# ATmega324PB_Xplained_Pro_EDBG.net
KiCad netlist of a schematic drawn in Altium Designer
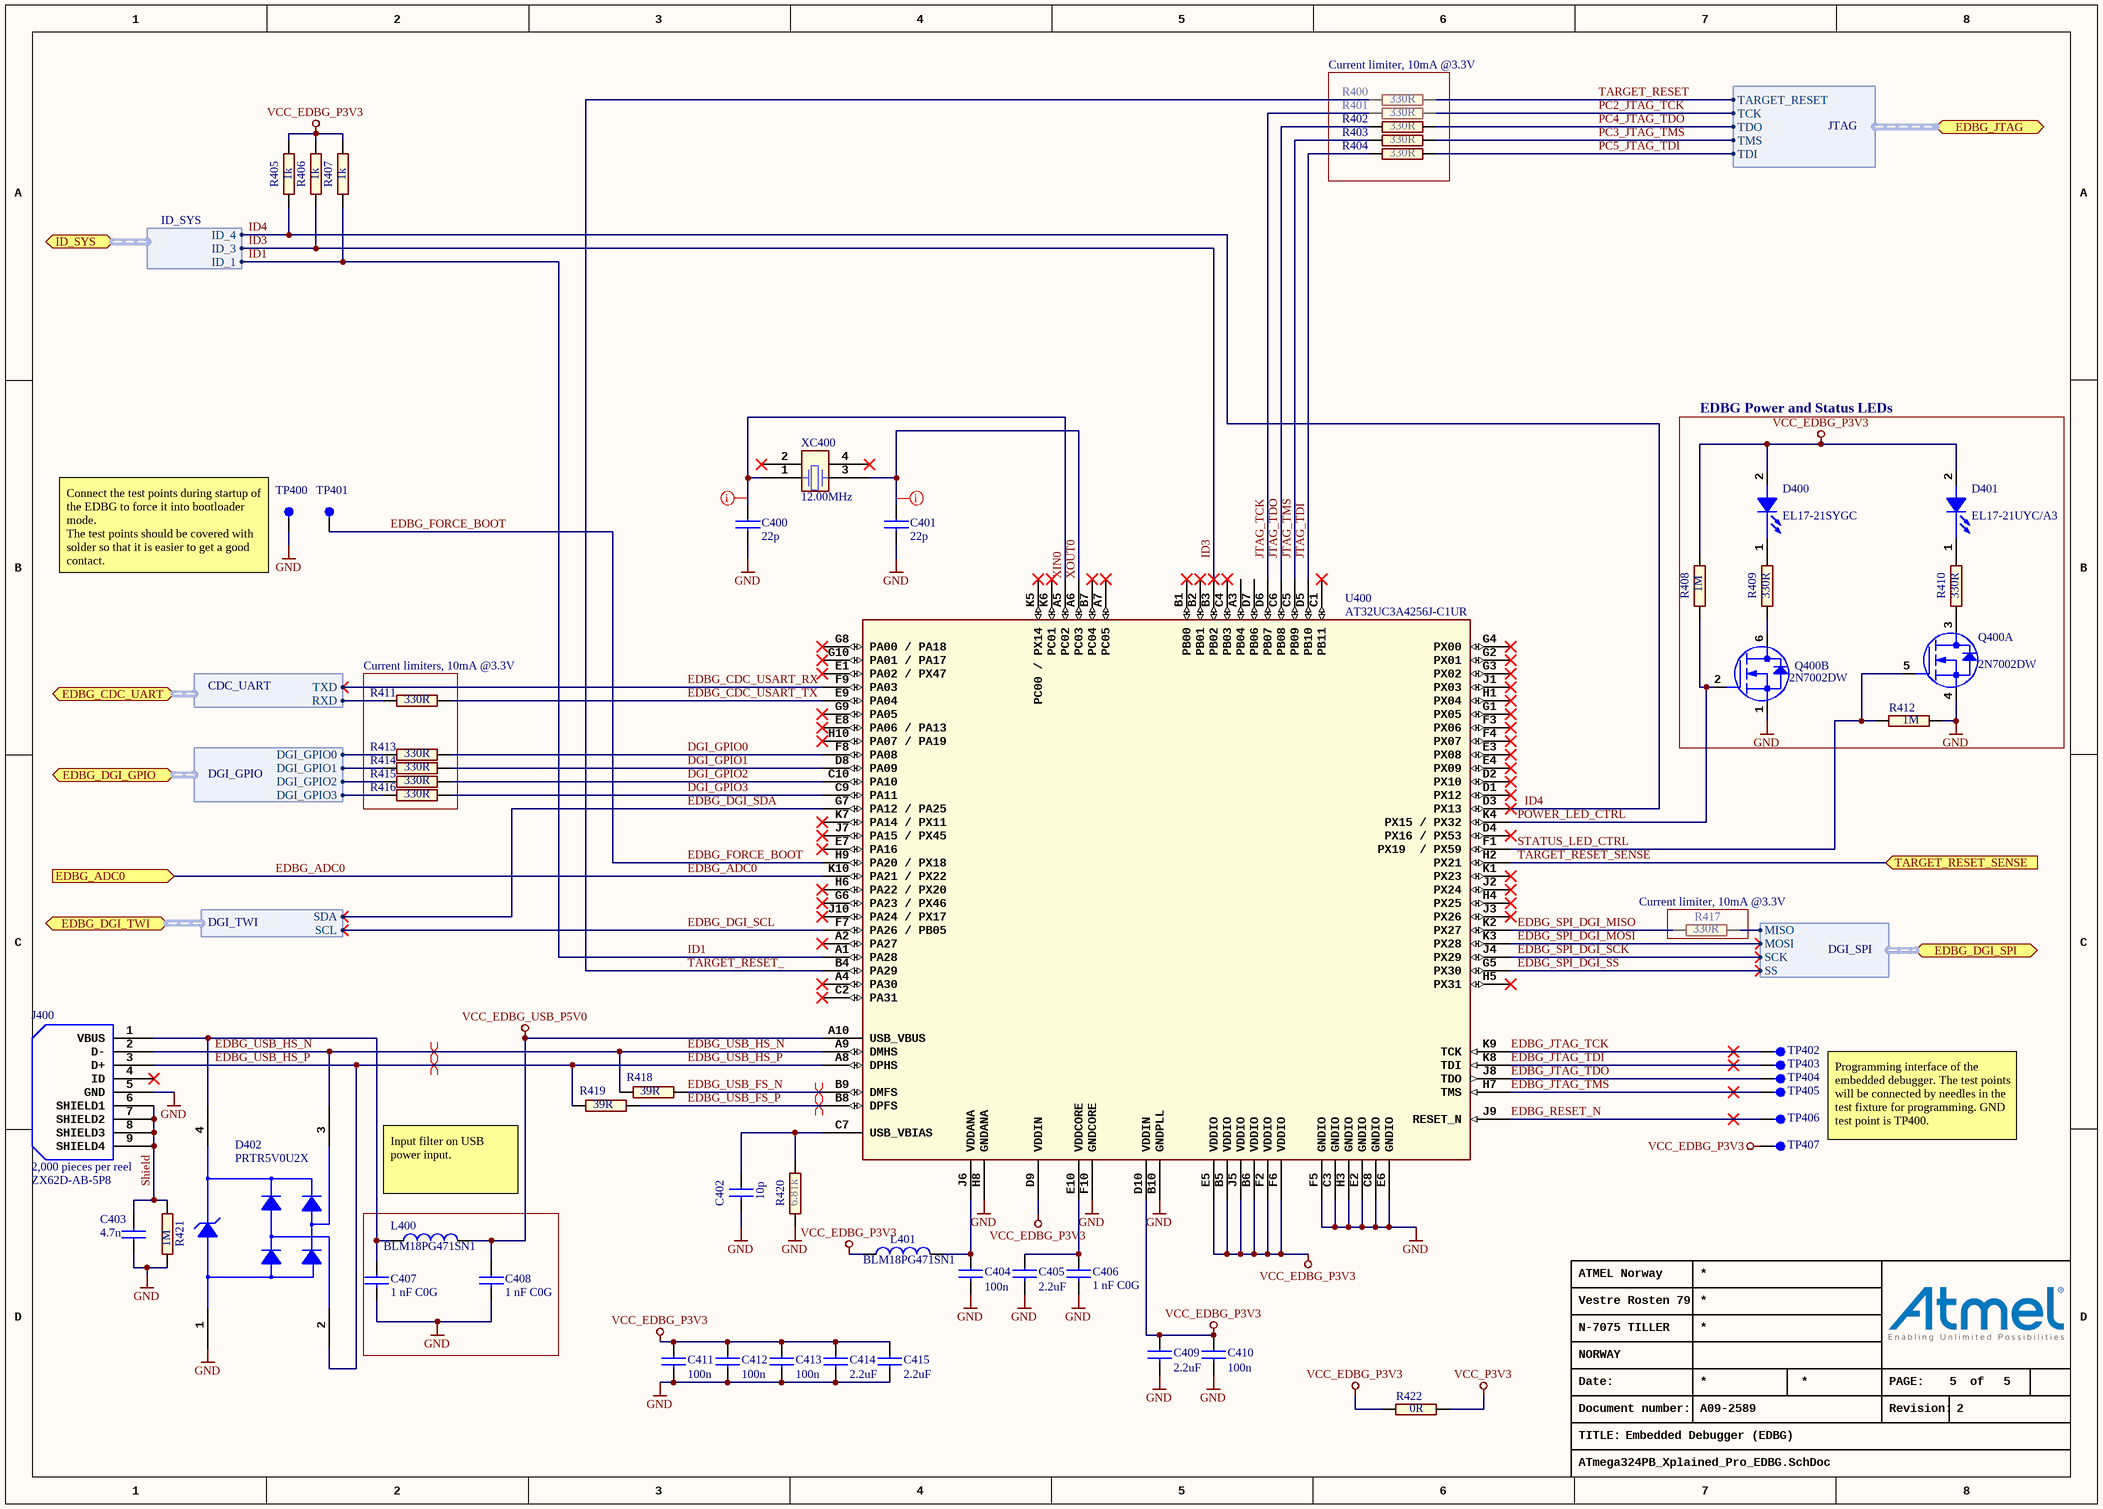
[diagram p0: ATmega324PB_Xplained_Pro_EDBG.SchDoc]

(export (version "E")
  (design (tool "Eeschema 10.0.6"))
  (components
    (comp (ref "C400")
      (value "22p")
      (footprint "AP1-00053")
      (description "Ceramic capacitor, SMD 0402, NP0, 50V, +/-5%")
      (fields (field (name "TOLERANCE") "50V, +/-5%"))
      (libsource (lib "AltiumDbLib") (part "CAP-NONPOL"))
    )
    (comp (ref "C401")
      (value "22p")
      (footprint "AP1-00053")
      (description "Ceramic capacitor, SMD 0402, NP0, 50V, +/-5%")
      (fields (field (name "TOLERANCE") "50V, +/-5%"))
      (libsource (lib "AltiumDbLib") (part "CAP-NONPOL"))
    )
    (comp (ref "C402")
      (value "10p")
      (footprint "AP1-00053")
      (description "Ceramic capacitor, SMD 0402, NP0, 50V, +/-5%")
      (fields (field (name "TOLERANCE") "50V, +/-5%"))
      (libsource (lib "AltiumDbLib") (part "CAP-NONPOL"))
    )
    (comp (ref "C403")
      (value "4.7n")
      (footprint "AP1-00053")
      (description "Ceramic capacitor, SMD 0402, X7R, 25V, +/-10%")
      (fields (field (name "TOLERANCE") "25V, +/-10%"))
      (libsource (lib "AltiumDbLib") (part "CAP-NONPOL"))
    )
    (comp (ref "C404")
      (value "100n")
      (footprint "AP1-00053")
      (description "Ceramic capacitor, SMD 0402, X7R, 16V, +/-10%")
      (fields (field (name "TOLERANCE") "16V, +/-10%") (field (name "MANUFACTURER") "Kemet"))
      (libsource (lib "AltiumDbLib") (part "CAP-NONPOL"))
    )
    (comp (ref "C405")
      (value "2.2uF")
      (footprint "AP1-00053")
      (description "Ceramic capacitor, SMD 0402, X5R, 6.3V, +/-20%")
      (fields (field (name "TOLERANCE") "Â±20%") (field (name "MANUFACTURER") "Kemet"))
      (libsource (lib "AltiumDbLib") (part "CAP-NONPOL"))
    )
    (comp (ref "C406")
      (value "1 nF C0G")
      (footprint "AP1-00053")
      (description "Ceramic capacitor, SMD 0402, C0G, 50V, +/-5%")
      (fields (field (name "TOLERANCE") "5%") (field (name "MANUFACTURER") "Murata"))
      (libsource (lib "AltiumDbLib") (part "CAP-NONPOL"))
    )
    (comp (ref "C407")
      (value "1 nF C0G")
      (footprint "AP1-00053")
      (description "Ceramic capacitor, SMD 0402, C0G, 50V, +/-5%")
      (fields (field (name "TOLERANCE") "5%") (field (name "MANUFACTURER") "Murata"))
      (libsource (lib "AltiumDbLib") (part "CAP-NONPOL"))
    )
    (comp (ref "C408")
      (value "1 nF C0G")
      (footprint "AP1-00053")
      (description "Ceramic capacitor, SMD 0402, C0G, 50V, +/-5%")
      (fields (field (name "TOLERANCE") "5%") (field (name "MANUFACTURER") "Murata"))
      (libsource (lib "AltiumDbLib") (part "CAP-NONPOL"))
    )
    (comp (ref "C409")
      (value "2.2uF")
      (footprint "AP1-00053")
      (description "Ceramic capacitor, SMD 0402, X5R, 6.3V, +/-20%")
      (fields (field (name "TOLERANCE") "Â±20%") (field (name "MANUFACTURER") "Kemet"))
      (libsource (lib "AltiumDbLib") (part "CAP-NONPOL"))
    )
    (comp (ref "C410")
      (value "100n")
      (footprint "AP1-00053")
      (description "Ceramic capacitor, SMD 0402, X7R, 16V, +/-10%")
      (fields (field (name "TOLERANCE") "16V, +/-10%") (field (name "MANUFACTURER") "Kemet"))
      (libsource (lib "AltiumDbLib") (part "CAP-NONPOL"))
    )
    (comp (ref "C411")
      (value "100n")
      (footprint "AP1-00053")
      (description "Ceramic capacitor, SMD 0402, X7R, 16V, +/-10%")
      (fields (field (name "TOLERANCE") "16V, +/-10%") (field (name "MANUFACTURER") "Kemet"))
      (libsource (lib "AltiumDbLib") (part "CAP-NONPOL"))
    )
    (comp (ref "C412")
      (value "100n")
      (footprint "AP1-00053")
      (description "Ceramic capacitor, SMD 0402, X7R, 16V, +/-10%")
      (fields (field (name "TOLERANCE") "16V, +/-10%") (field (name "MANUFACTURER") "Kemet"))
      (libsource (lib "AltiumDbLib") (part "CAP-NONPOL"))
    )
    (comp (ref "C413")
      (value "100n")
      (footprint "AP1-00053")
      (description "Ceramic capacitor, SMD 0402, X7R, 16V, +/-10%")
      (fields (field (name "TOLERANCE") "16V, +/-10%") (field (name "MANUFACTURER") "Kemet"))
      (libsource (lib "AltiumDbLib") (part "CAP-NONPOL"))
    )
    (comp (ref "C414")
      (value "2.2uF")
      (footprint "AP1-00053")
      (description "Ceramic capacitor, SMD 0402, X5R, 6.3V, +/-20%")
      (fields (field (name "TOLERANCE") "Â±20%") (field (name "MANUFACTURER") "Kemet"))
      (libsource (lib "AltiumDbLib") (part "CAP-NONPOL"))
    )
    (comp (ref "C415")
      (value "2.2uF")
      (footprint "AP1-00053")
      (description "Ceramic capacitor, SMD 0402, X5R, 6.3V, +/-20%")
      (fields (field (name "TOLERANCE") "Â±20%") (field (name "MANUFACTURER") "Kemet"))
      (libsource (lib "AltiumDbLib") (part "CAP-NONPOL"))
    )
    (comp (ref "D400")
      (value "EL17-21SYGC")
      (footprint "AP4-00013")
      (description "LED, Green, Wave length=575nm, SMD 0805, ±70°")
      (fields (field (name "MANUFACTURER") "Everlight"))
      (libsource (lib "AltiumDbLib") (part "LED_12"))
    )
    (comp (ref "D401")
      (value "EL17-21UYC/A3")
      (footprint "AP4-00013")
      (description "LED, Yellow, Wave length=591nm, SMD 0805, ±70°")
      (fields (field (name "MANUFACTURER") "Everlight") (field (name "MPN") "17-21UYC/S530-A3/TR8"))
      (libsource (lib "AltiumDbLib") (part "LED_12"))
    )
    (comp (ref "D402")
      (value "PRTR5V0U2X")
      (footprint "AP4-00001")
      (description "Double rail-to-rail USB ESD protection diode")
      (fields
        (field (name "MANUFACTURER") "NXP")
        (field (name "Comment") "Changed manufacturer from Philips to NXP.")
      )
      (libsource (lib "AltiumDbLib") (part "PRTR5V0U2X"))
    )
    (comp (ref "J400")
      (value "2,000 pieces per reel")
      (footprint "AP8-00852")
      (description "Micro USB AB Connector, Standard SMT + DIP")
      (fields
        (field (name "ALTIUM_VALUE") "ZX62D-AB-5P8")
        (field (name "MANUFACTURER") "HIROSE")
        (field (name "MPN") "ZX62D-AB-5P8")
      )
      (libsource (lib "AltiumDbLib") (part "USB_AB"))
    )
    (comp (ref "L400")
      (value "BLM18PG471SN1")
      (footprint "AP3-00005")
      (description "SMD RF inductor 0603. Z=470Ohm (@100MHz), Max R(dc)=0.65Ohm, Max current=1A")
      (fields (field (name "TOLERANCE") "±25%") (field (name "MANUFACTURER") "Murata"))
      (libsource (lib "AltiumDbLib") (part "INDUCTOR"))
    )
    (comp (ref "L401")
      (value "BLM18PG471SN1")
      (footprint "AP3-00005")
      (description "SMD RF inductor 0603. Z=470Ohm (@100MHz), Max R(dc)=0.65Ohm, Max current=1A")
      (fields (field (name "TOLERANCE") "±25%") (field (name "MANUFACTURER") "Murata"))
      (libsource (lib "AltiumDbLib") (part "INDUCTOR"))
    )
    (comp (ref "Q400")
      (value "2N7002DW")
      (footprint "AP5-00001")
      (description "Dual N-Channel MOSFET, 60V, 115mA cont,RDS(ON) < 7.5 Ohm @50mA@5V, SOT-363")
      (fields
        (field (name "MANUFACTURER") "Fairchild")
        (field (name "Comment") "Same as 2N7002 but with two MOSFETs in one package")
      )
      (libsource (lib "AltiumDbLib") (part "MOSFET_DUAL_N_S2G2D1S1G1D2"))
    )
    (comp (ref "R400")
      (value "330R")
      (footprint "AP2-00000")
      (description "Thick film resistor, SMD 0402, 1/16W, 1%")
      (fields (field (name "TOLERANCE") "1 %"))
      (libsource (lib "AltiumDbLib") (part "R2"))
    )
    (comp (ref "R401")
      (value "330R")
      (footprint "AP2-00000")
      (description "Thick film resistor, SMD 0402, 1/16W, 1%")
      (fields (field (name "TOLERANCE") "1 %"))
      (libsource (lib "AltiumDbLib") (part "R2"))
    )
    (comp (ref "R402")
      (value "330R")
      (footprint "AP2-00000")
      (description "Thick film resistor, SMD 0402, 1/16W, 1%")
      (fields (field (name "TOLERANCE") "1 %"))
      (libsource (lib "AltiumDbLib") (part "R2"))
    )
    (comp (ref "R403")
      (value "330R")
      (footprint "AP2-00000")
      (description "Thick film resistor, SMD 0402, 1/16W, 1%")
      (fields (field (name "TOLERANCE") "1 %"))
      (libsource (lib "AltiumDbLib") (part "R2"))
    )
    (comp (ref "R404")
      (value "330R")
      (footprint "AP2-00000")
      (description "Thick film resistor, SMD 0402, 1/16W, 1%")
      (fields (field (name "TOLERANCE") "1 %"))
      (libsource (lib "AltiumDbLib") (part "R2"))
    )
    (comp (ref "R405")
      (value "1k")
      (footprint "AP2-00000")
      (description "Thick film resistor, SMD 0402, 1/16W, 1%")
      (fields (field (name "TOLERANCE") "1 %"))
      (libsource (lib "") (part "R2_2"))
    )
    (comp (ref "R406")
      (value "1k")
      (footprint "AP2-00000")
      (description "Thick film resistor, SMD 0402, 1/16W, 1%")
      (fields (field (name "TOLERANCE") "1 %"))
      (libsource (lib "") (part "R2_2"))
    )
    (comp (ref "R407")
      (value "1k")
      (footprint "AP2-00000")
      (description "Thick film resistor, SMD 0402, 1/16W, 1%")
      (fields (field (name "TOLERANCE") "1 %"))
      (libsource (lib "") (part "R2_2"))
    )
    (comp (ref "R408")
      (value "1M")
      (footprint "AP2-00000")
      (description "Thick film resistor, SMD 0402, 1/16W, 1%")
      (fields (field (name "TOLERANCE") "1 %"))
      (libsource (lib "") (part "R2_2"))
    )
    (comp (ref "R409")
      (value "330R")
      (footprint "AP2-00000")
      (description "Thick film resistor, SMD 0402, 1/16W, 1%")
      (fields (field (name "TOLERANCE") "1 %"))
      (libsource (lib "") (part "R2_2"))
    )
    (comp (ref "R410")
      (value "330R")
      (footprint "AP2-00000")
      (description "Thick film resistor, SMD 0402, 1/16W, 1%")
      (fields (field (name "TOLERANCE") "1 %"))
      (libsource (lib "") (part "R2_2"))
    )
    (comp (ref "R411")
      (value "330R")
      (footprint "AP2-00000")
      (description "Thick film resistor, SMD 0402, 1/16W, 1%")
      (fields (field (name "TOLERANCE") "1 %"))
      (libsource (lib "AltiumDbLib") (part "R2"))
    )
    (comp (ref "R412")
      (value "1M")
      (footprint "AP2-00000")
      (description "Thick film resistor, SMD 0402, 1/16W, 1%")
      (fields (field (name "TOLERANCE") "1 %"))
      (libsource (lib "") (part "R2_1"))
    )
    (comp (ref "R413")
      (value "330R")
      (footprint "AP2-00000")
      (description "Thick film resistor, SMD 0402, 1/16W, 1%")
      (fields (field (name "TOLERANCE") "1 %"))
      (libsource (lib "AltiumDbLib") (part "R2"))
    )
    (comp (ref "R414")
      (value "330R")
      (footprint "AP2-00000")
      (description "Thick film resistor, SMD 0402, 1/16W, 1%")
      (fields (field (name "TOLERANCE") "1 %"))
      (libsource (lib "AltiumDbLib") (part "R2"))
    )
    (comp (ref "R415")
      (value "330R")
      (footprint "AP2-00000")
      (description "Thick film resistor, SMD 0402, 1/16W, 1%")
      (fields (field (name "TOLERANCE") "1 %"))
      (libsource (lib "AltiumDbLib") (part "R2"))
    )
    (comp (ref "R416")
      (value "330R")
      (footprint "AP2-00000")
      (description "Thick film resistor, SMD 0402, 1/16W, 1%")
      (fields (field (name "TOLERANCE") "1 %"))
      (libsource (lib "AltiumDbLib") (part "R2"))
    )
    (comp (ref "R417")
      (value "330R")
      (footprint "AP2-00000")
      (description "Thick film resistor, SMD 0402, 1/16W, 1%")
      (fields (field (name "TOLERANCE") "1 %"))
      (libsource (lib "AltiumDbLib") (part "R2"))
    )
    (comp (ref "R418")
      (value "39R")
      (footprint "AP2-00011")
      (description "Thick film resistor, SMD 0402, 1/16W, 1%")
      (fields (field (name "TOLERANCE") "1 %"))
      (libsource (lib "") (part "R2_3"))
    )
    (comp (ref "R419")
      (value "39R")
      (footprint "AP2-00011")
      (description "Thick film resistor, SMD 0402, 1/16W, 1%")
      (fields (field (name "TOLERANCE") "1 %"))
      (libsource (lib "") (part "R2_3"))
    )
    (comp (ref "R420")
      (value "6.81k")
      (footprint "AP2-00011")
      (description "Thick film resistor, SMD 0402, 1/16W, 1%")
      (fields (field (name "TOLERANCE") "1%"))
      (libsource (lib "") (part "R2_2"))
    )
    (comp (ref "R421")
      (value "1M")
      (footprint "AP2-00011")
      (description "Thick film resistor, SMD 0402, 1/16W, 1%")
      (fields (field (name "TOLERANCE") "1 %"))
      (libsource (lib "") (part "R2_4"))
    )
    (comp (ref "R422")
      (value "0R")
      (footprint "AP2-00000")
      (description "Thick film resistor, SMD 0402, 1/16W, 1%")
      (fields (field (name "TOLERANCE") "1 %") (field (name "MANUFACTURER") "(n/a)"))
      (libsource (lib "AltiumDbLib") (part "R2"))
    )
    (comp (ref "TP400")
      (value "~")
      (footprint "AP8-00010")
      (description "Single SMD testpad")
      (libsource (lib "AltiumDbLib") (part "TESTPOINT"))
    )
    (comp (ref "TP401")
      (value "~")
      (footprint "AP8-00010")
      (description "Single SMD testpad")
      (libsource (lib "AltiumDbLib") (part "TESTPOINT"))
    )
    (comp (ref "TP402")
      (value "~")
      (footprint "AP8-00010")
      (description "Single SMD testpad")
      (libsource (lib "AltiumDbLib") (part "TESTPOINT"))
    )
    (comp (ref "TP403")
      (value "~")
      (footprint "AP8-00010")
      (description "Single SMD testpad")
      (libsource (lib "AltiumDbLib") (part "TESTPOINT"))
    )
    (comp (ref "TP404")
      (value "~")
      (footprint "AP8-00010")
      (description "Single SMD testpad")
      (libsource (lib "AltiumDbLib") (part "TESTPOINT"))
    )
    (comp (ref "TP405")
      (value "~")
      (footprint "AP8-00010")
      (description "Single SMD testpad")
      (libsource (lib "AltiumDbLib") (part "TESTPOINT"))
    )
    (comp (ref "TP406")
      (value "~")
      (footprint "AP8-00010")
      (description "Single SMD testpad")
      (libsource (lib "AltiumDbLib") (part "TESTPOINT"))
    )
    (comp (ref "TP407")
      (value "~")
      (footprint "AP8-00010")
      (description "Single SMD testpad")
      (libsource (lib "AltiumDbLib") (part "TESTPOINT"))
    )
    (comp (ref "U400")
      (value "AT32UC3A4256J-C1UR")
      (footprint "AP6-00206")
      (description "AVR 32-bit RISC MCU")
      (fields (field (name "MANUFACTURER") "ATMEL") (field (name "Comment") "100 ball VFBGA"))
      (libsource (lib "AltiumDbLib") (part "AT32UC3A4_VFBGA"))
    )
    (comp (ref "XC400")
      (value "12.00MHz")
      (footprint "AP7-00039")
      (description "Fox FQ5032B 12.0MHz SMD crystal 738B-12")
      (fields (field (name "TOLERANCE") "Â±30ppm") (field (name "MANUFACTURER") "Fox  Electronics"))
      (libsource (lib "AltiumDbLib") (part "CRYSTAL1324"))
    )
  )
  (nets
    (net (code "7") (name "/DGI_GPIO0") (class "Default")
      (node (ref "R413") (pin "2") (pinfunction "2_2") (pintype "passive"))
      (node (ref "U400") (pin "F8") (pinfunction "PA08_F8") (pintype "bidirectional"))
    )
    (net (code "8") (name "/DGI_GPIO1") (class "Default")
      (node (ref "R414") (pin "2") (pinfunction "2_2") (pintype "passive"))
      (node (ref "U400") (pin "D8") (pinfunction "PA09_D8") (pintype "bidirectional"))
    )
    (net (code "9") (name "/DGI_GPIO2") (class "Default")
      (node (ref "R415") (pin "2") (pinfunction "2_2") (pintype "passive"))
      (node (ref "U400") (pin "C10") (pinfunction "PA10_C10") (pintype "bidirectional"))
    )
    (net (code "10") (name "/DGI_GPIO3") (class "Default")
      (node (ref "R416") (pin "2") (pinfunction "2_2") (pintype "passive"))
      (node (ref "U400") (pin "C9") (pinfunction "PA11_C9") (pintype "bidirectional"))
    )
    (net (code "11") (name "/EDBG_ADC0") (class "Default")
      (node (ref "U400") (pin "K10") (pinfunction "PA21_/_PX22_K10") (pintype "bidirectional"))
    )
    (net (code "12") (name "/EDBG_CDC_USART_RX") (class "Default")
      (node (ref "U400") (pin "F9") (pinfunction "PA03_F9") (pintype "bidirectional+no_connect"))
    )
    (net (code "13") (name "/EDBG_CDC_USART_TX") (class "Default")
      (node (ref "R411") (pin "2") (pinfunction "2_2") (pintype "passive"))
      (node (ref "U400") (pin "E9") (pinfunction "PA04_E9") (pintype "bidirectional"))
    )
    (net (code "14") (name "/EDBG_DGI_SCL") (class "Default")
      (node (ref "U400") (pin "F7") (pinfunction "PA26_/_PB05_F7") (pintype "bidirectional+no_connect"))
    )
    (net (code "15") (name "/EDBG_DGI_SDA") (class "Default")
      (node (ref "U400") (pin "G7") (pinfunction "PA12_/_PA25_G7") (pintype "bidirectional+no_connect"))
    )
    (net (code "16") (name "/EDBG_FORCE_BOOT") (class "Default")
      (node (ref "TP401") (pin "1") (pinfunction "1_1") (pintype "passive"))
      (node (ref "U400") (pin "H9") (pinfunction "PA20_/_PX18_H9") (pintype "bidirectional"))
    )
    (net (code "17") (name "/EDBG_JTAG_TCK") (class "Default")
      (node (ref "TP402") (pin "1") (pinfunction "1_1") (pintype "passive"))
      (node (ref "U400") (pin "K9") (pinfunction "TCK_K9") (pintype "input"))
    )
    (net (code "18") (name "/EDBG_JTAG_TDI") (class "Default")
      (node (ref "TP403") (pin "1") (pinfunction "1_1") (pintype "passive"))
      (node (ref "U400") (pin "K8") (pinfunction "TDI_K8") (pintype "input"))
    )
    (net (code "19") (name "/EDBG_JTAG_TDO") (class "Default")
      (node (ref "TP404") (pin "1") (pinfunction "1_1") (pintype "passive"))
      (node (ref "U400") (pin "J8") (pinfunction "TDO_J8") (pintype "output"))
    )
    (net (code "20") (name "/EDBG_JTAG_TMS") (class "Default")
      (node (ref "TP405") (pin "1") (pinfunction "1_1") (pintype "passive"))
      (node (ref "U400") (pin "H7") (pinfunction "TMS_H7") (pintype "input"))
    )
    (net (code "21") (name "/EDBG_RESET_N") (class "Default")
      (node (ref "TP406") (pin "1") (pinfunction "1_1") (pintype "passive"))
      (node (ref "U400") (pin "J9") (pinfunction "RESET_N_J9") (pintype "input"))
    )
    (net (code "22") (name "/EDBG_SPI_DGI_MISO") (class "Default")
      (node (ref "R417") (pin "1") (pinfunction "1_1") (pintype "passive"))
      (node (ref "U400") (pin "K2") (pinfunction "PX27_K2") (pintype "bidirectional"))
    )
    (net (code "23") (name "/EDBG_SPI_DGI_MOSI") (class "Default")
      (node (ref "U400") (pin "K3") (pinfunction "PX28_K3") (pintype "bidirectional+no_connect"))
    )
    (net (code "24") (name "/EDBG_SPI_DGI_SCK") (class "Default")
      (node (ref "U400") (pin "J4") (pinfunction "PX29_J4") (pintype "bidirectional+no_connect"))
    )
    (net (code "25") (name "/EDBG_SPI_DGI_SS") (class "Default")
      (node (ref "U400") (pin "G5") (pinfunction "PX30_G5") (pintype "bidirectional+no_connect"))
    )
    (net (code "26") (name "/EDBG_USB_FS_N") (class "Default")
      (node (ref "R418") (pin "2") (pinfunction "2_2") (pintype "passive"))
      (node (ref "U400") (pin "B9") (pinfunction "DMFS_B9") (pintype "bidirectional"))
    )
    (net (code "27") (name "/EDBG_USB_FS_P") (class "Default")
      (node (ref "R419") (pin "2") (pinfunction "2_2") (pintype "passive"))
      (node (ref "U400") (pin "B8") (pinfunction "DPFS_B8") (pintype "bidirectional"))
    )
    (net (code "28") (name "/EDBG_USB_HS_N") (class "Default")
      (node (ref "D402") (pin "3") (pinfunction "I/O_2_3") (pintype "passive"))
      (node (ref "J400") (pin "2") (pinfunction "D-_2") (pintype "passive"))
      (node (ref "R418") (pin "1") (pinfunction "1_1") (pintype "passive"))
      (node (ref "U400") (pin "A9") (pinfunction "DMHS_A9") (pintype "bidirectional"))
    )
    (net (code "29") (name "/EDBG_USB_HS_P") (class "Default")
      (node (ref "D402") (pin "2") (pinfunction "I/O_1_2") (pintype "passive"))
      (node (ref "J400") (pin "3") (pinfunction "D+_3") (pintype "passive"))
      (node (ref "R419") (pin "1") (pinfunction "1_1") (pintype "passive"))
      (node (ref "U400") (pin "A8") (pinfunction "DPHS_A8") (pintype "bidirectional"))
    )
    (net (code "30") (name "/ID1") (class "Default")
      (node (ref "R407") (pin "1") (pinfunction "1_1") (pintype "passive"))
      (node (ref "U400") (pin "A1") (pinfunction "PA28_A1") (pintype "bidirectional"))
    )
    (net (code "31") (name "/ID3") (class "Default")
      (node (ref "R406") (pin "1") (pinfunction "1_1") (pintype "passive"))
      (node (ref "U400") (pin "B3") (pinfunction "PB02_B3") (pintype "bidirectional"))
    )
    (net (code "32") (name "/ID4") (class "Default")
      (node (ref "R405") (pin "1") (pinfunction "1_1") (pintype "passive"))
      (node (ref "U400") (pin "D3") (pinfunction "PX13_D3") (pintype "bidirectional"))
    )
    (net (code "33") (name "/JTAG_TCK") (class "Default")
      (node (ref "R401") (pin "1") (pinfunction "1_1") (pintype "passive"))
      (node (ref "U400") (pin "D6") (pinfunction "PB07_D6") (pintype "bidirectional"))
    )
    (net (code "34") (name "/JTAG_TDI") (class "Default")
      (node (ref "R404") (pin "1") (pinfunction "1_1") (pintype "passive"))
      (node (ref "U400") (pin "D5") (pinfunction "PB10_D5") (pintype "bidirectional"))
    )
    (net (code "35") (name "/JTAG_TDO") (class "Default")
      (node (ref "R402") (pin "1") (pinfunction "1_1") (pintype "passive"))
      (node (ref "U400") (pin "C6") (pinfunction "PB08_C6") (pintype "bidirectional"))
    )
    (net (code "36") (name "/JTAG_TMS") (class "Default")
      (node (ref "R403") (pin "1") (pinfunction "1_1") (pintype "passive"))
      (node (ref "U400") (pin "C5") (pinfunction "PB09_C5") (pintype "bidirectional"))
    )
    (net (code "37") (name "/MISO") (class "Default")
      (node (ref "R417") (pin "2") (pinfunction "2_2") (pintype "passive"))
    )
    (net (code "38") (name "/PC2_JTAG_TCK") (class "Default")
      (node (ref "R401") (pin "2") (pinfunction "2_2") (pintype "passive"))
    )
    (net (code "39") (name "/PC3_JTAG_TMS") (class "Default")
      (node (ref "R403") (pin "2") (pinfunction "2_2") (pintype "passive"))
    )
    (net (code "40") (name "/PC4_JTAG_TDO") (class "Default")
      (node (ref "R402") (pin "2") (pinfunction "2_2") (pintype "passive"))
    )
    (net (code "41") (name "/PC5_JTAG_TDI") (class "Default")
      (node (ref "R404") (pin "2") (pinfunction "2_2") (pintype "passive"))
    )
    (net (code "42") (name "/POWER_LED_CTRL") (class "Default")
      (node (ref "Q400") (pin "2") (pinfunction "G2_2") (pintype "passive"))
      (node (ref "R408") (pin "1") (pinfunction "1_1") (pintype "passive"))
      (node (ref "U400") (pin "K4") (pinfunction "PX15_/_PX32_K4") (pintype "bidirectional"))
    )
    (net (code "43") (name "/RXD") (class "Default")
      (node (ref "R411") (pin "1") (pinfunction "1_1") (pintype "passive"))
    )
    (net (code "44") (name "/STATUS_LED_CTRL") (class "Default")
      (node (ref "Q400") (pin "5") (pinfunction "G1_5") (pintype "passive"))
      (node (ref "R412") (pin "2") (pinfunction "2_2") (pintype "passive"))
      (node (ref "U400") (pin "F1") (pinfunction "PX19__/_PX59_F1") (pintype "bidirectional"))
    )
    (net (code "45") (name "/Shield") (class "Default")
      (node (ref "C403") (pin "2") (pinfunction "2_2") (pintype "passive"))
      (node (ref "J400") (pin "6") (pinfunction "SHIELD1_6") (pintype "passive"))
      (node (ref "J400") (pin "7") (pinfunction "SHIELD2_7") (pintype "passive"))
      (node (ref "J400") (pin "8") (pinfunction "SHIELD3_8") (pintype "passive"))
      (node (ref "J400") (pin "9") (pinfunction "SHIELD4_9") (pintype "passive"))
      (node (ref "R421") (pin "2") (pinfunction "2_2") (pintype "passive"))
    )
    (net (code "46") (name "/TARGET_RESET") (class "Default")
      (node (ref "R400") (pin "2") (pinfunction "2_2") (pintype "passive"))
    )
    (net (code "47") (name "/TARGET_RESET_") (class "Default")
      (node (ref "R400") (pin "1") (pinfunction "1_1") (pintype "passive"))
      (node (ref "U400") (pin "B4") (pinfunction "PA29_B4") (pintype "bidirectional"))
    )
    (net (code "48") (name "/TARGET_RESET_SENSE") (class "Default")
      (node (ref "U400") (pin "H2") (pinfunction "PX21_H2") (pintype "bidirectional"))
    )
    (net (code "49") (name "/XIN0") (class "Default")
      (node (ref "C400") (pin "1") (pinfunction "1_1") (pintype "passive"))
      (node (ref "U400") (pin "A5") (pinfunction "PC02_A5") (pintype "bidirectional"))
      (node (ref "XC400") (pin "1") (pinfunction "1_1") (pintype "passive"))
    )
    (net (code "50") (name "/XOUT0") (class "Default")
      (node (ref "C401") (pin "1") (pinfunction "1_1") (pintype "passive"))
      (node (ref "U400") (pin "A6") (pinfunction "PC03_A6") (pintype "bidirectional"))
      (node (ref "XC400") (pin "3") (pinfunction "3_3") (pintype "passive"))
    )
    (net (code "57") (name "GND") (class "Default")
      (node (ref "C400") (pin "2") (pinfunction "2_2") (pintype "passive"))
      (node (ref "C401") (pin "2") (pinfunction "2_2") (pintype "passive"))
      (node (ref "C402") (pin "2") (pinfunction "2_2") (pintype "passive"))
      (node (ref "C403") (pin "1") (pinfunction "1_1") (pintype "passive"))
      (node (ref "C404") (pin "2") (pinfunction "2_2") (pintype "passive"))
      (node (ref "C405") (pin "2") (pinfunction "2_2") (pintype "passive"))
      (node (ref "C406") (pin "2") (pinfunction "2_2") (pintype "passive"))
      (node (ref "C407") (pin "2") (pinfunction "2_2") (pintype "passive"))
      (node (ref "C408") (pin "2") (pinfunction "2_2") (pintype "passive"))
      (node (ref "C409") (pin "2") (pinfunction "2_2") (pintype "passive"))
      (node (ref "C410") (pin "2") (pinfunction "2_2") (pintype "passive"))
      (node (ref "C411") (pin "2") (pinfunction "2_2") (pintype "passive"))
      (node (ref "C412") (pin "2") (pinfunction "2_2") (pintype "passive"))
      (node (ref "C413") (pin "2") (pinfunction "2_2") (pintype "passive"))
      (node (ref "C414") (pin "2") (pinfunction "2_2") (pintype "passive"))
      (node (ref "C415") (pin "2") (pinfunction "2_2") (pintype "passive"))
      (node (ref "D402") (pin "1") (pinfunction "GND_1") (pintype "passive"))
      (node (ref "J400") (pin "5") (pinfunction "GND_5") (pintype "passive"))
      (node (ref "Q400") (pin "1") (pinfunction "S2_1") (pintype "passive"))
      (node (ref "Q400") (pin "4") (pinfunction "S1_4") (pintype "passive"))
      (node (ref "R412") (pin "1") (pinfunction "1_1") (pintype "passive"))
      (node (ref "R420") (pin "1") (pinfunction "1_1") (pintype "passive"))
      (node (ref "R421") (pin "1") (pinfunction "1_1") (pintype "passive"))
      (node (ref "TP400") (pin "1") (pinfunction "1_1") (pintype "passive"))
      (node (ref "U400") (pin "B10") (pinfunction "GNDPLL_B10") (pintype "power_in"))
      (node (ref "U400") (pin "C3") (pinfunction "GNDIO_C3") (pintype "power_in"))
      (node (ref "U400") (pin "C8") (pinfunction "GNDIO_C8") (pintype "power_in"))
      (node (ref "U400") (pin "E2") (pinfunction "GNDIO_E2") (pintype "power_in"))
      (node (ref "U400") (pin "E6") (pinfunction "GNDIO_E6") (pintype "power_in"))
      (node (ref "U400") (pin "F10") (pinfunction "GNDCORE_F10") (pintype "power_in"))
      (node (ref "U400") (pin "F5") (pinfunction "GNDIO_F5") (pintype "power_in"))
      (node (ref "U400") (pin "H3") (pinfunction "GNDIO_H3") (pintype "power_in"))
      (node (ref "U400") (pin "H8") (pinfunction "GNDANA_H8") (pintype "power_in"))
    )
    (net (code "58") (name "Net-(D400-CATHODE)") (class "Default")
      (node (ref "D400") (pin "1") (pinfunction "CATHODE_1") (pintype "passive"))
      (node (ref "R409") (pin "2") (pinfunction "2_2") (pintype "passive"))
    )
    (net (code "59") (name "Net-(D401-CATHODE)") (class "Default")
      (node (ref "D401") (pin "1") (pinfunction "CATHODE_1") (pintype "passive"))
      (node (ref "R410") (pin "2") (pinfunction "2_2") (pintype "passive"))
    )
    (net (code "60") (name "Net-(D402-VCC)") (class "Default")
      (node (ref "C407") (pin "1") (pinfunction "1_1") (pintype "passive"))
      (node (ref "D402") (pin "4") (pinfunction "VCC_4") (pintype "passive"))
      (node (ref "J400") (pin "1") (pinfunction "VBUS_1") (pintype "passive"))
      (node (ref "L400") (pin "1") (pinfunction "1_1") (pintype "passive"))
    )
    (net (code "61") (name "Net-(Q400A-D1)") (class "Default")
      (node (ref "Q400") (pin "3") (pinfunction "D1_3") (pintype "passive"))
      (node (ref "R410") (pin "1") (pinfunction "1_1") (pintype "passive"))
    )
    (net (code "62") (name "Net-(Q400B-D2)") (class "Default")
      (node (ref "Q400") (pin "6") (pinfunction "D2_6") (pintype "passive"))
      (node (ref "R409") (pin "1") (pinfunction "1_1") (pintype "passive"))
    )
    (net (code "63") (name "Net-(U400-USB_VBIAS)") (class "Default")
      (node (ref "C402") (pin "1") (pinfunction "1_1") (pintype "passive"))
      (node (ref "R420") (pin "2") (pinfunction "2_2") (pintype "passive"))
      (node (ref "U400") (pin "C7") (pinfunction "USB_VBIAS_C7") (pintype "power_in"))
    )
    (net (code "64") (name "Net-(U400-VDDANA)") (class "Default")
      (node (ref "C404") (pin "1") (pinfunction "1_1") (pintype "passive"))
      (node (ref "L401") (pin "2") (pinfunction "2_2") (pintype "passive"))
      (node (ref "U400") (pin "J6") (pinfunction "VDDANA_J6") (pintype "power_in"))
    )
    (net (code "65") (name "Net-(U400-VDDCORE)") (class "Default")
      (node (ref "C405") (pin "1") (pinfunction "1_1") (pintype "passive"))
      (node (ref "C406") (pin "1") (pinfunction "1_1") (pintype "passive"))
      (node (ref "U400") (pin "E10") (pinfunction "VDDCORE_E10") (pintype "power_in"))
    )
    (net (code "66") (name "VCC_EDBG_P3V3") (class "Default")
      (node (ref "C409") (pin "1") (pinfunction "1_1") (pintype "passive"))
      (node (ref "C410") (pin "1") (pinfunction "1_1") (pintype "passive"))
      (node (ref "C411") (pin "1") (pinfunction "1_1") (pintype "passive"))
      (node (ref "C412") (pin "1") (pinfunction "1_1") (pintype "passive"))
      (node (ref "C413") (pin "1") (pinfunction "1_1") (pintype "passive"))
      (node (ref "C414") (pin "1") (pinfunction "1_1") (pintype "passive"))
      (node (ref "C415") (pin "1") (pinfunction "1_1") (pintype "passive"))
      (node (ref "D400") (pin "2") (pinfunction "ANODE_2") (pintype "passive"))
      (node (ref "D401") (pin "2") (pinfunction "ANODE_2") (pintype "passive"))
      (node (ref "L401") (pin "1") (pinfunction "1_1") (pintype "passive"))
      (node (ref "R405") (pin "2") (pinfunction "2_2") (pintype "passive"))
      (node (ref "R406") (pin "2") (pinfunction "2_2") (pintype "passive"))
      (node (ref "R407") (pin "2") (pinfunction "2_2") (pintype "passive"))
      (node (ref "R408") (pin "2") (pinfunction "2_2") (pintype "passive"))
      (node (ref "R422") (pin "1") (pinfunction "1_1") (pintype "passive"))
      (node (ref "TP407") (pin "1") (pinfunction "1_1") (pintype "passive"))
      (node (ref "U400") (pin "B5") (pinfunction "VDDIO_B5") (pintype "power_in"))
      (node (ref "U400") (pin "B6") (pinfunction "VDDIO_B6") (pintype "power_in"))
      (node (ref "U400") (pin "D10") (pinfunction "VDDIN_D10") (pintype "power_in"))
      (node (ref "U400") (pin "D9") (pinfunction "VDDIN_D9") (pintype "power_in"))
      (node (ref "U400") (pin "E5") (pinfunction "VDDIO_E5") (pintype "power_in"))
      (node (ref "U400") (pin "F2") (pinfunction "VDDIO_F2") (pintype "power_in"))
      (node (ref "U400") (pin "F6") (pinfunction "VDDIO_F6") (pintype "power_in"))
      (node (ref "U400") (pin "J5") (pinfunction "VDDIO_J5") (pintype "power_in"))
    )
    (net (code "67") (name "VCC_EDBG_USB_P5V0") (class "Default")
      (node (ref "C408") (pin "1") (pinfunction "1_1") (pintype "passive"))
      (node (ref "L400") (pin "2") (pinfunction "2_2") (pintype "passive"))
      (node (ref "U400") (pin "A10") (pinfunction "USB_VBUS_A10") (pintype "power_in"))
    )
    (net (code "68") (name "VCC_P3V3") (class "Default")
      (node (ref "R422") (pin "2") (pinfunction "2_2") (pintype "passive"))
    )
    (net (code "69") (name "unconnected-(J400-ID-Pad4)") (class "Default")
      (node (ref "J400") (pin "4") (pinfunction "ID_4") (pintype "passive+no_connect"))
    )
    (net (code "70") (name "unconnected-(R413-Pad1)") (class "Default")
      (node (ref "R413") (pin "1") (pinfunction "1_1") (pintype "passive"))
    )
    (net (code "71") (name "unconnected-(R414-Pad1)") (class "Default")
      (node (ref "R414") (pin "1") (pinfunction "1_1") (pintype "passive"))
    )
    (net (code "72") (name "unconnected-(R415-Pad1)") (class "Default")
      (node (ref "R415") (pin "1") (pinfunction "1_1") (pintype "passive"))
    )
    (net (code "73") (name "unconnected-(R416-Pad1)") (class "Default")
      (node (ref "R416") (pin "1") (pinfunction "1_1") (pintype "passive"))
    )
    (net (code "74") (name "unconnected-(U400-PA00_{slash}_PA18-PadG8)") (class "Default")
      (node (ref "U400") (pin "G8") (pinfunction "PA00_/_PA18_G8") (pintype "bidirectional+no_connect"))
    )
    (net (code "75") (name "unconnected-(U400-PA01_{slash}_PA17-PadG10)") (class "Default")
      (node (ref "U400") (pin "G10") (pinfunction "PA01_/_PA17_G10") (pintype "bidirectional+no_connect"))
    )
    (net (code "76") (name "unconnected-(U400-PA02_{slash}_PX47-PadE1)") (class "Default")
      (node (ref "U400") (pin "E1") (pinfunction "PA02_/_PX47_E1") (pintype "bidirectional+no_connect"))
    )
    (net (code "77") (name "unconnected-(U400-PA05-PadG9)") (class "Default")
      (node (ref "U400") (pin "G9") (pinfunction "PA05_G9") (pintype "bidirectional+no_connect"))
    )
    (net (code "78") (name "unconnected-(U400-PA06_{slash}_PA13-PadE8)") (class "Default")
      (node (ref "U400") (pin "E8") (pinfunction "PA06_/_PA13_E8") (pintype "bidirectional+no_connect"))
    )
    (net (code "79") (name "unconnected-(U400-PA07_{slash}_PA19-PadH10)") (class "Default")
      (node (ref "U400") (pin "H10") (pinfunction "PA07_/_PA19_H10") (pintype "bidirectional+no_connect"))
    )
    (net (code "80") (name "unconnected-(U400-PA14_{slash}_PX11-PadK7)") (class "Default")
      (node (ref "U400") (pin "K7") (pinfunction "PA14_/_PX11_K7") (pintype "bidirectional+no_connect"))
    )
    (net (code "81") (name "unconnected-(U400-PA15_{slash}_PX45-PadJ7)") (class "Default")
      (node (ref "U400") (pin "J7") (pinfunction "PA15_/_PX45_J7") (pintype "bidirectional+no_connect"))
    )
    (net (code "82") (name "unconnected-(U400-PA16-PadE7)") (class "Default")
      (node (ref "U400") (pin "E7") (pinfunction "PA16_E7") (pintype "bidirectional+no_connect"))
    )
    (net (code "83") (name "unconnected-(U400-PA22_{slash}_PX20-PadH6)") (class "Default")
      (node (ref "U400") (pin "H6") (pinfunction "PA22_/_PX20_H6") (pintype "bidirectional+no_connect"))
    )
    (net (code "84") (name "unconnected-(U400-PA23_{slash}_PX46-PadG6)") (class "Default")
      (node (ref "U400") (pin "G6") (pinfunction "PA23_/_PX46_G6") (pintype "bidirectional+no_connect"))
    )
    (net (code "85") (name "unconnected-(U400-PA24_{slash}_PX17-PadJ10)") (class "Default")
      (node (ref "U400") (pin "J10") (pinfunction "PA24_/_PX17_J10") (pintype "bidirectional+no_connect"))
    )
    (net (code "86") (name "unconnected-(U400-PA27-PadA2)") (class "Default")
      (node (ref "U400") (pin "A2") (pinfunction "PA27_A2") (pintype "bidirectional+no_connect"))
    )
    (net (code "87") (name "unconnected-(U400-PA30-PadA4)") (class "Default")
      (node (ref "U400") (pin "A4") (pinfunction "PA30_A4") (pintype "bidirectional+no_connect"))
    )
    (net (code "88") (name "unconnected-(U400-PA31-PadC2)") (class "Default")
      (node (ref "U400") (pin "C2") (pinfunction "PA31_C2") (pintype "bidirectional+no_connect"))
    )
    (net (code "89") (name "unconnected-(U400-PB00-PadB1)") (class "Default")
      (node (ref "U400") (pin "B1") (pinfunction "PB00_B1") (pintype "bidirectional+no_connect"))
    )
    (net (code "90") (name "unconnected-(U400-PB01-PadB2)") (class "Default")
      (node (ref "U400") (pin "B2") (pinfunction "PB01_B2") (pintype "bidirectional+no_connect"))
    )
    (net (code "91") (name "unconnected-(U400-PB03-PadC4)") (class "Default")
      (node (ref "U400") (pin "C4") (pinfunction "PB03_C4") (pintype "bidirectional+no_connect"))
    )
    (net (code "92") (name "unconnected-(U400-PB04-PadA3)") (class "Default")
      (node (ref "U400") (pin "A3") (pinfunction "PB04_A3") (pintype "bidirectional"))
    )
    (net (code "93") (name "unconnected-(U400-PB06-PadD7)") (class "Default")
      (node (ref "U400") (pin "D7") (pinfunction "PB06_D7") (pintype "bidirectional"))
    )
    (net (code "94") (name "unconnected-(U400-PB11-PadC1)") (class "Default")
      (node (ref "U400") (pin "C1") (pinfunction "PB11_C1") (pintype "bidirectional+no_connect"))
    )
    (net (code "95") (name "unconnected-(U400-PC00_{slash}_PX14-PadK5)") (class "Default")
      (node (ref "U400") (pin "K5") (pinfunction "PC00_/_PX14_K5") (pintype "bidirectional+no_connect"))
    )
    (net (code "96") (name "unconnected-(U400-PC01-PadK6)") (class "Default")
      (node (ref "U400") (pin "K6") (pinfunction "PC01_K6") (pintype "bidirectional+no_connect"))
    )
    (net (code "97") (name "unconnected-(U400-PC04-PadB7)") (class "Default")
      (node (ref "U400") (pin "B7") (pinfunction "PC04_B7") (pintype "bidirectional+no_connect"))
    )
    (net (code "98") (name "unconnected-(U400-PC05-PadA7)") (class "Default")
      (node (ref "U400") (pin "A7") (pinfunction "PC05_A7") (pintype "bidirectional+no_connect"))
    )
    (net (code "99") (name "unconnected-(U400-PX00-PadG4)") (class "Default")
      (node (ref "U400") (pin "G4") (pinfunction "PX00_G4") (pintype "bidirectional+no_connect"))
    )
    (net (code "100") (name "unconnected-(U400-PX01-PadG2)") (class "Default")
      (node (ref "U400") (pin "G2") (pinfunction "PX01_G2") (pintype "bidirectional+no_connect"))
    )
    (net (code "101") (name "unconnected-(U400-PX02-PadG3)") (class "Default")
      (node (ref "U400") (pin "G3") (pinfunction "PX02_G3") (pintype "bidirectional+no_connect"))
    )
    (net (code "102") (name "unconnected-(U400-PX03-PadJ1)") (class "Default")
      (node (ref "U400") (pin "J1") (pinfunction "PX03_J1") (pintype "bidirectional+no_connect"))
    )
    (net (code "103") (name "unconnected-(U400-PX04-PadH1)") (class "Default")
      (node (ref "U400") (pin "H1") (pinfunction "PX04_H1") (pintype "bidirectional+no_connect"))
    )
    (net (code "104") (name "unconnected-(U400-PX05-PadG1)") (class "Default")
      (node (ref "U400") (pin "G1") (pinfunction "PX05_G1") (pintype "bidirectional+no_connect"))
    )
    (net (code "105") (name "unconnected-(U400-PX06-PadF3)") (class "Default")
      (node (ref "U400") (pin "F3") (pinfunction "PX06_F3") (pintype "bidirectional+no_connect"))
    )
    (net (code "106") (name "unconnected-(U400-PX07-PadF4)") (class "Default")
      (node (ref "U400") (pin "F4") (pinfunction "PX07_F4") (pintype "bidirectional+no_connect"))
    )
    (net (code "107") (name "unconnected-(U400-PX08-PadE3)") (class "Default")
      (node (ref "U400") (pin "E3") (pinfunction "PX08_E3") (pintype "bidirectional+no_connect"))
    )
    (net (code "108") (name "unconnected-(U400-PX09-PadE4)") (class "Default")
      (node (ref "U400") (pin "E4") (pinfunction "PX09_E4") (pintype "bidirectional+no_connect"))
    )
    (net (code "109") (name "unconnected-(U400-PX10-PadD2)") (class "Default")
      (node (ref "U400") (pin "D2") (pinfunction "PX10_D2") (pintype "bidirectional+no_connect"))
    )
    (net (code "110") (name "unconnected-(U400-PX12-PadD1)") (class "Default")
      (node (ref "U400") (pin "D1") (pinfunction "PX12_D1") (pintype "bidirectional+no_connect"))
    )
    (net (code "111") (name "unconnected-(U400-PX16_{slash}_PX53-PadD4)") (class "Default")
      (node (ref "U400") (pin "D4") (pinfunction "PX16_/_PX53_D4") (pintype "bidirectional+no_connect"))
    )
    (net (code "112") (name "unconnected-(U400-PX23-PadK1)") (class "Default")
      (node (ref "U400") (pin "K1") (pinfunction "PX23_K1") (pintype "bidirectional+no_connect"))
    )
    (net (code "113") (name "unconnected-(U400-PX24-PadJ2)") (class "Default")
      (node (ref "U400") (pin "J2") (pinfunction "PX24_J2") (pintype "bidirectional+no_connect"))
    )
    (net (code "114") (name "unconnected-(U400-PX25-PadH4)") (class "Default")
      (node (ref "U400") (pin "H4") (pinfunction "PX25_H4") (pintype "bidirectional+no_connect"))
    )
    (net (code "115") (name "unconnected-(U400-PX26-PadJ3)") (class "Default")
      (node (ref "U400") (pin "J3") (pinfunction "PX26_J3") (pintype "bidirectional+no_connect"))
    )
    (net (code "116") (name "unconnected-(U400-PX31-PadH5)") (class "Default")
      (node (ref "U400") (pin "H5") (pinfunction "PX31_H5") (pintype "bidirectional+no_connect"))
    )
    (net (code "117") (name "unconnected-(XC400-Pad2)") (class "Default")
      (node (ref "XC400") (pin "2") (pinfunction "2_2") (pintype "passive+no_connect"))
    )
    (net (code "118") (name "unconnected-(XC400-Pad4)") (class "Default")
      (node (ref "XC400") (pin "4") (pinfunction "4_4") (pintype "passive+no_connect"))
    )
  )
)
